# arduino-uno-shield.net
KiCad netlist of a schematic drawn in EAGLE
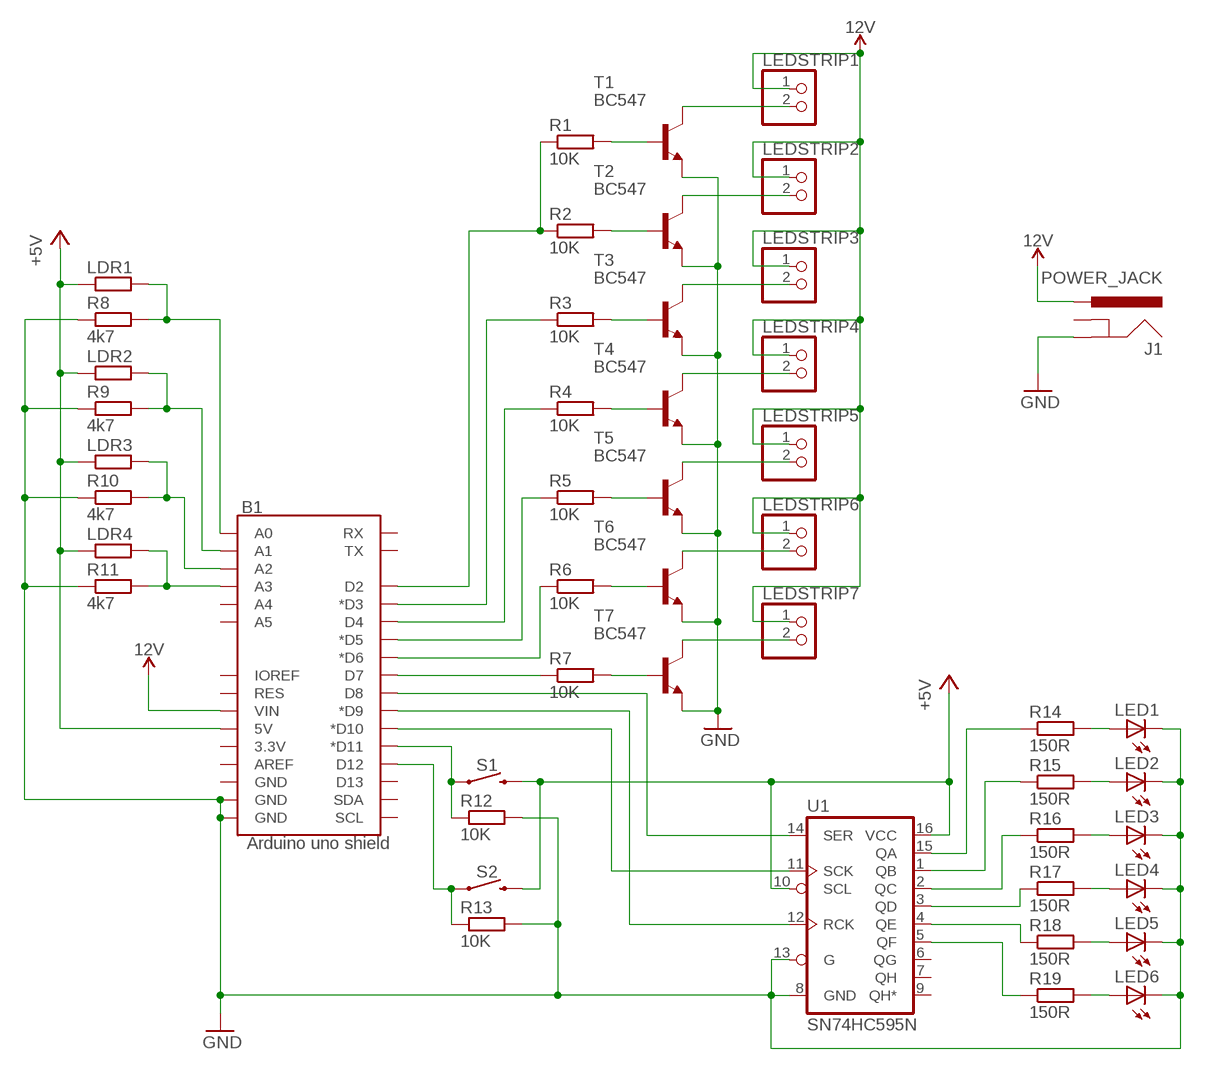
[diagram p0: schematic, sheet 1]

(export (version "E")
  (design (tool "Eeschema 10.0.6"))
  (components
    (comp (ref "B1")
      (value "Arduino uno shield")
      (footprint "eagle-import:UNO_R3_SHIELD_NOLABELS_LOCK")
      (libsource (lib "eagle-import") (part "ARDUINO_UNO_R3_SHIELDUNO_R3_SHIELD_NOLABELS_LOCK"))
    )
    (comp (ref "J1")
      (value "POWER_JACK")
      (footprint "eagle-import:POWER_JACK_PTH")
      (libsource (lib "eagle-import") (part "POWER_JACK"))
    )
    (comp (ref "LDR1")
      (value "R-EU_0204/5")
      (footprint "eagle-import:0204_5")
      (libsource (lib "eagle-import") (part "R-EU_0204/5"))
    )
    (comp (ref "LDR2")
      (value "R-EU_0204/5")
      (footprint "eagle-import:0204_5")
      (libsource (lib "eagle-import") (part "R-EU_0204/5"))
    )
    (comp (ref "LDR3")
      (value "R-EU_0204/5")
      (footprint "eagle-import:0204_5")
      (libsource (lib "eagle-import") (part "R-EU_0204/5"))
    )
    (comp (ref "LDR4")
      (value "R-EU_0204/5")
      (footprint "eagle-import:0204_5")
      (libsource (lib "eagle-import") (part "R-EU_0204/5"))
    )
    (comp (ref "LED1")
      (value "LED5MM")
      (footprint "eagle-import:LED5MM")
      (libsource (lib "eagle-import") (part "LED5MM"))
    )
    (comp (ref "LED2")
      (value "LED5MM")
      (footprint "eagle-import:LED5MM")
      (libsource (lib "eagle-import") (part "LED5MM"))
    )
    (comp (ref "LED3")
      (value "LED5MM")
      (footprint "eagle-import:LED5MM")
      (libsource (lib "eagle-import") (part "LED5MM"))
    )
    (comp (ref "LED4")
      (value "LED5MM")
      (footprint "eagle-import:LED5MM")
      (libsource (lib "eagle-import") (part "LED5MM"))
    )
    (comp (ref "LED5")
      (value "LED5MM")
      (footprint "eagle-import:LED5MM")
      (libsource (lib "eagle-import") (part "LED5MM"))
    )
    (comp (ref "LED6")
      (value "LED5MM")
      (footprint "eagle-import:LED5MM")
      (libsource (lib "eagle-import") (part "LED5MM"))
    )
    (comp (ref "LEDSTRIP1")
      (value "PINHD-1X2")
      (footprint "eagle-import:1X02")
      (libsource (lib "eagle-import") (part "PINHD-1X2"))
    )
    (comp (ref "LEDSTRIP2")
      (value "PINHD-1X2")
      (footprint "eagle-import:1X02")
      (libsource (lib "eagle-import") (part "PINHD-1X2"))
    )
    (comp (ref "LEDSTRIP3")
      (value "PINHD-1X2")
      (footprint "eagle-import:1X02")
      (libsource (lib "eagle-import") (part "PINHD-1X2"))
    )
    (comp (ref "LEDSTRIP4")
      (value "PINHD-1X2")
      (footprint "eagle-import:1X02")
      (libsource (lib "eagle-import") (part "PINHD-1X2"))
    )
    (comp (ref "LEDSTRIP5")
      (value "PINHD-1X2")
      (footprint "eagle-import:1X02")
      (libsource (lib "eagle-import") (part "PINHD-1X2"))
    )
    (comp (ref "LEDSTRIP6")
      (value "PINHD-1X2")
      (footprint "eagle-import:1X02")
      (libsource (lib "eagle-import") (part "PINHD-1X2"))
    )
    (comp (ref "LEDSTRIP7")
      (value "PINHD-1X2")
      (footprint "eagle-import:1X02")
      (libsource (lib "eagle-import") (part "PINHD-1X2"))
    )
    (comp (ref "R1")
      (value "10K")
      (footprint "eagle-import:0204_5")
      (libsource (lib "eagle-import") (part "R-EU_0204/5"))
    )
    (comp (ref "R2")
      (value "10K")
      (footprint "eagle-import:0204_5")
      (libsource (lib "eagle-import") (part "R-EU_0204/5"))
    )
    (comp (ref "R3")
      (value "10K")
      (footprint "eagle-import:0204_5")
      (libsource (lib "eagle-import") (part "R-EU_0204/5"))
    )
    (comp (ref "R4")
      (value "10K")
      (footprint "eagle-import:0204_5")
      (libsource (lib "eagle-import") (part "R-EU_0204/5"))
    )
    (comp (ref "R5")
      (value "10K")
      (footprint "eagle-import:0204_5")
      (libsource (lib "eagle-import") (part "R-EU_0204/5"))
    )
    (comp (ref "R6")
      (value "10K")
      (footprint "eagle-import:0204_5")
      (libsource (lib "eagle-import") (part "R-EU_0204/5"))
    )
    (comp (ref "R7")
      (value "10K")
      (footprint "eagle-import:0204_5")
      (libsource (lib "eagle-import") (part "R-EU_0204/5"))
    )
    (comp (ref "R8")
      (value "4k7")
      (footprint "eagle-import:0204_5")
      (libsource (lib "eagle-import") (part "R-EU_0204/5"))
    )
    (comp (ref "R9")
      (value "4k7")
      (footprint "eagle-import:0204_5")
      (libsource (lib "eagle-import") (part "R-EU_0204/5"))
    )
    (comp (ref "R10")
      (value "4k7")
      (footprint "eagle-import:0204_5")
      (libsource (lib "eagle-import") (part "R-EU_0204/5"))
    )
    (comp (ref "R11")
      (value "4k7")
      (footprint "eagle-import:0204_5")
      (libsource (lib "eagle-import") (part "R-EU_0204/5"))
    )
    (comp (ref "R12")
      (value "10K")
      (footprint "eagle-import:0204_5")
      (libsource (lib "eagle-import") (part "R-EU_0204/5"))
    )
    (comp (ref "R13")
      (value "10K")
      (footprint "eagle-import:0204_5")
      (libsource (lib "eagle-import") (part "R-EU_0204/5"))
    )
    (comp (ref "R14")
      (value "150R")
      (footprint "eagle-import:0204_5")
      (libsource (lib "eagle-import") (part "R-EU_0204/5"))
    )
    (comp (ref "R15")
      (value "150R")
      (footprint "eagle-import:0204_5")
      (libsource (lib "eagle-import") (part "R-EU_0204/5"))
    )
    (comp (ref "R16")
      (value "150R")
      (footprint "eagle-import:0204_5")
      (libsource (lib "eagle-import") (part "R-EU_0204/5"))
    )
    (comp (ref "R17")
      (value "150R")
      (footprint "eagle-import:0204_5")
      (libsource (lib "eagle-import") (part "R-EU_0204/5"))
    )
    (comp (ref "R18")
      (value "150R")
      (footprint "eagle-import:0204_5")
      (libsource (lib "eagle-import") (part "R-EU_0204/5"))
    )
    (comp (ref "R19")
      (value "150R")
      (footprint "eagle-import:0204_5")
      (libsource (lib "eagle-import") (part "R-EU_0204/5"))
    )
    (comp (ref "S1")
      (value "MOMENTARY-SWITCH-SPST-PTH-6.0MM")
      (footprint "eagle-import:TACTILE_SWITCH_PTH_6.0MM")
      (libsource (lib "eagle-import") (part "MOMENTARY-SWITCH-SPST-PTH-6.0MM"))
    )
    (comp (ref "S2")
      (value "MOMENTARY-SWITCH-SPST-PTH-6.0MM")
      (footprint "eagle-import:TACTILE_SWITCH_PTH_6.0MM")
      (libsource (lib "eagle-import") (part "MOMENTARY-SWITCH-SPST-PTH-6.0MM"))
    )
    (comp (ref "T1")
      (value "BC547")
      (footprint "eagle-import:TO92")
      (libsource (lib "eagle-import") (part "BC547"))
    )
    (comp (ref "T2")
      (value "BC547")
      (footprint "eagle-import:TO92")
      (libsource (lib "eagle-import") (part "BC547"))
    )
    (comp (ref "T3")
      (value "BC547")
      (footprint "eagle-import:TO92")
      (libsource (lib "eagle-import") (part "BC547"))
    )
    (comp (ref "T4")
      (value "BC547")
      (footprint "eagle-import:TO92")
      (libsource (lib "eagle-import") (part "BC547"))
    )
    (comp (ref "T5")
      (value "BC547")
      (footprint "eagle-import:TO92")
      (libsource (lib "eagle-import") (part "BC547"))
    )
    (comp (ref "T6")
      (value "BC547")
      (footprint "eagle-import:TO92")
      (libsource (lib "eagle-import") (part "BC547"))
    )
    (comp (ref "T7")
      (value "BC547")
      (footprint "eagle-import:TO92")
      (libsource (lib "eagle-import") (part "BC547"))
    )
    (comp (ref "U1")
      (value "SN74HC595N")
      (footprint "eagle-import:DIP16")
      (libsource (lib "eagle-import") (part "74595NHC"))
    )
  )
  (nets
    (net (code "1") (name "+5V") (class "Default")
      (node (ref "B1") (pin "5V") (pinfunction "5V_5V") (pintype "bidirectional"))
      (node (ref "LDR1") (pin "1") (pinfunction "1_1") (pintype "passive"))
      (node (ref "LDR2") (pin "1") (pinfunction "1_1") (pintype "passive"))
      (node (ref "LDR3") (pin "1") (pinfunction "1_1") (pintype "passive"))
      (node (ref "LDR4") (pin "1") (pinfunction "1_1") (pintype "passive"))
      (node (ref "S1") (pin "3") (pinfunction "2_3") (pintype "passive"))
      (node (ref "S2") (pin "3") (pinfunction "2_3") (pintype "passive"))
      (node (ref "U1") (pin "10") (pinfunction "SCL_10") (pintype "input"))
      (node (ref "U1") (pin "16") (pinfunction "VCC_16") (pintype "power_in"))
    )
    (net (code "2") (name "12V") (class "Default")
      (node (ref "B1") (pin "VIN") (pinfunction "VIN_VIN") (pintype "bidirectional"))
      (node (ref "J1") (pin "PWR") (pinfunction "PWR_PWR") (pintype "bidirectional"))
      (node (ref "LEDSTRIP1") (pin "1") (pinfunction "1_1") (pintype "passive"))
      (node (ref "LEDSTRIP2") (pin "1") (pinfunction "1_1") (pintype "passive"))
      (node (ref "LEDSTRIP3") (pin "1") (pinfunction "1_1") (pintype "passive"))
      (node (ref "LEDSTRIP4") (pin "1") (pinfunction "1_1") (pintype "passive"))
      (node (ref "LEDSTRIP5") (pin "1") (pinfunction "1_1") (pintype "passive"))
      (node (ref "LEDSTRIP6") (pin "1") (pinfunction "1_1") (pintype "passive"))
      (node (ref "LEDSTRIP7") (pin "1") (pinfunction "1_1") (pintype "passive"))
    )
    (net (code "3") (name "GND") (class "Default")
      (node (ref "B1") (pin "GND@0") (pinfunction "GND_GND@0") (pintype "bidirectional"))
      (node (ref "B1") (pin "GND@1") (pinfunction "GND_GND@1") (pintype "bidirectional"))
      (node (ref "J1") (pin "GND") (pinfunction "GND_GND") (pintype "bidirectional"))
      (node (ref "LED1") (pin "K") (pinfunction "C_K") (pintype "passive"))
      (node (ref "LED2") (pin "K") (pinfunction "C_K") (pintype "passive"))
      (node (ref "LED3") (pin "K") (pinfunction "C_K") (pintype "passive"))
      (node (ref "LED4") (pin "K") (pinfunction "C_K") (pintype "passive"))
      (node (ref "LED5") (pin "K") (pinfunction "C_K") (pintype "passive"))
      (node (ref "LED6") (pin "K") (pinfunction "C_K") (pintype "passive"))
      (node (ref "R10") (pin "1") (pinfunction "1_1") (pintype "passive"))
      (node (ref "R11") (pin "1") (pinfunction "1_1") (pintype "passive"))
      (node (ref "R12") (pin "2") (pinfunction "2_2") (pintype "passive"))
      (node (ref "R13") (pin "2") (pinfunction "2_2") (pintype "passive"))
      (node (ref "R8") (pin "1") (pinfunction "1_1") (pintype "passive"))
      (node (ref "R9") (pin "1") (pinfunction "1_1") (pintype "passive"))
      (node (ref "T1") (pin "1") (pinfunction "E_1") (pintype "passive"))
      (node (ref "T2") (pin "1") (pinfunction "E_1") (pintype "passive"))
      (node (ref "T3") (pin "1") (pinfunction "E_1") (pintype "passive"))
      (node (ref "T4") (pin "1") (pinfunction "E_1") (pintype "passive"))
      (node (ref "T5") (pin "1") (pinfunction "E_1") (pintype "passive"))
      (node (ref "T6") (pin "1") (pinfunction "E_1") (pintype "passive"))
      (node (ref "T7") (pin "1") (pinfunction "E_1") (pintype "passive"))
      (node (ref "U1") (pin "13") (pinfunction "G_13") (pintype "input"))
      (node (ref "U1") (pin "8") (pinfunction "GND_8") (pintype "power_in"))
    )
    (net (code "4") (name "Net-(B1-*D3)") (class "Default")
      (node (ref "B1") (pin "D3") (pinfunction "*D3_D3") (pintype "bidirectional"))
      (node (ref "R3") (pin "1") (pinfunction "1_1") (pintype "passive"))
    )
    (net (code "5") (name "Net-(B1-*D5)") (class "Default")
      (node (ref "B1") (pin "D5") (pinfunction "*D5_D5") (pintype "bidirectional"))
      (node (ref "R5") (pin "1") (pinfunction "1_1") (pintype "passive"))
    )
    (net (code "6") (name "Net-(B1-*D6)") (class "Default")
      (node (ref "B1") (pin "D6") (pinfunction "*D6_D6") (pintype "bidirectional"))
      (node (ref "R6") (pin "1") (pinfunction "1_1") (pintype "passive"))
    )
    (net (code "7") (name "Net-(B1-*D9)") (class "Default")
      (node (ref "B1") (pin "D9") (pinfunction "*D9_D9") (pintype "bidirectional"))
      (node (ref "U1") (pin "12") (pinfunction "RCK_12") (pintype "input"))
    )
    (net (code "8") (name "Net-(B1-*D10)") (class "Default")
      (node (ref "B1") (pin "D10") (pinfunction "*D10_D10") (pintype "bidirectional"))
      (node (ref "U1") (pin "11") (pinfunction "SCK_11") (pintype "input"))
    )
    (net (code "9") (name "Net-(B1-*D11)") (class "Default")
      (node (ref "B1") (pin "D11") (pinfunction "*D11_D11") (pintype "bidirectional"))
      (node (ref "R12") (pin "1") (pinfunction "1_1") (pintype "passive"))
      (node (ref "S1") (pin "1") (pinfunction "1_1") (pintype "passive"))
    )
    (net (code "10") (name "Net-(B1-PadA0)") (class "Default")
      (node (ref "B1") (pin "A0") (pinfunction "A0_A0") (pintype "bidirectional"))
      (node (ref "LDR1") (pin "2") (pinfunction "2_2") (pintype "passive"))
      (node (ref "R8") (pin "2") (pinfunction "2_2") (pintype "passive"))
    )
    (net (code "11") (name "Net-(B1-PadA1)") (class "Default")
      (node (ref "B1") (pin "A1") (pinfunction "A1_A1") (pintype "bidirectional"))
      (node (ref "LDR2") (pin "2") (pinfunction "2_2") (pintype "passive"))
      (node (ref "R9") (pin "2") (pinfunction "2_2") (pintype "passive"))
    )
    (net (code "12") (name "Net-(B1-PadA2)") (class "Default")
      (node (ref "B1") (pin "A2") (pinfunction "A2_A2") (pintype "bidirectional"))
      (node (ref "LDR3") (pin "2") (pinfunction "2_2") (pintype "passive"))
      (node (ref "R10") (pin "2") (pinfunction "2_2") (pintype "passive"))
    )
    (net (code "13") (name "Net-(B1-PadA3)") (class "Default")
      (node (ref "B1") (pin "A3") (pinfunction "A3_A3") (pintype "bidirectional"))
      (node (ref "LDR4") (pin "2") (pinfunction "2_2") (pintype "passive"))
      (node (ref "R11") (pin "2") (pinfunction "2_2") (pintype "passive"))
    )
    (net (code "14") (name "Net-(B1-PadD2)") (class "Default")
      (node (ref "B1") (pin "D2") (pinfunction "D2_D2") (pintype "bidirectional"))
      (node (ref "R1") (pin "1") (pinfunction "1_1") (pintype "passive"))
      (node (ref "R2") (pin "1") (pinfunction "1_1") (pintype "passive"))
    )
    (net (code "15") (name "Net-(B1-PadD4)") (class "Default")
      (node (ref "B1") (pin "D4") (pinfunction "D4_D4") (pintype "bidirectional"))
      (node (ref "R4") (pin "1") (pinfunction "1_1") (pintype "passive"))
    )
    (net (code "16") (name "Net-(B1-PadD7)") (class "Default")
      (node (ref "B1") (pin "D7") (pinfunction "D7_D7") (pintype "bidirectional"))
      (node (ref "R7") (pin "1") (pinfunction "1_1") (pintype "passive"))
    )
    (net (code "17") (name "Net-(B1-PadD12)") (class "Default")
      (node (ref "B1") (pin "D12") (pinfunction "D12_D12") (pintype "bidirectional"))
      (node (ref "R13") (pin "1") (pinfunction "1_1") (pintype "passive"))
      (node (ref "S2") (pin "1") (pinfunction "1_1") (pintype "passive"))
    )
    (net (code "18") (name "Net-(LED1-PadA)") (class "Default")
      (node (ref "LED1") (pin "A") (pinfunction "A_A") (pintype "passive"))
      (node (ref "R14") (pin "2") (pinfunction "2_2") (pintype "passive"))
    )
    (net (code "19") (name "Net-(LED2-PadA)") (class "Default")
      (node (ref "LED2") (pin "A") (pinfunction "A_A") (pintype "passive"))
      (node (ref "R15") (pin "2") (pinfunction "2_2") (pintype "passive"))
    )
    (net (code "20") (name "Net-(LED3-PadA)") (class "Default")
      (node (ref "LED3") (pin "A") (pinfunction "A_A") (pintype "passive"))
      (node (ref "R16") (pin "2") (pinfunction "2_2") (pintype "passive"))
    )
    (net (code "21") (name "Net-(LED4-PadA)") (class "Default")
      (node (ref "LED4") (pin "A") (pinfunction "A_A") (pintype "passive"))
      (node (ref "R17") (pin "2") (pinfunction "2_2") (pintype "passive"))
    )
    (net (code "22") (name "Net-(LED5-PadA)") (class "Default")
      (node (ref "LED5") (pin "A") (pinfunction "A_A") (pintype "passive"))
      (node (ref "R18") (pin "2") (pinfunction "2_2") (pintype "passive"))
    )
    (net (code "23") (name "Net-(LED6-PadA)") (class "Default")
      (node (ref "LED6") (pin "A") (pinfunction "A_A") (pintype "passive"))
      (node (ref "R19") (pin "2") (pinfunction "2_2") (pintype "passive"))
    )
    (net (code "24") (name "Net-(T1-B)") (class "Default")
      (node (ref "R1") (pin "2") (pinfunction "2_2") (pintype "passive"))
      (node (ref "T1") (pin "2") (pinfunction "B_2") (pintype "passive"))
    )
    (net (code "25") (name "Net-(T1-C)") (class "Default")
      (node (ref "LEDSTRIP1") (pin "2") (pinfunction "2_2") (pintype "passive"))
      (node (ref "T1") (pin "3") (pinfunction "C_3") (pintype "passive"))
    )
    (net (code "26") (name "Net-(T2-B)") (class "Default")
      (node (ref "R2") (pin "2") (pinfunction "2_2") (pintype "passive"))
      (node (ref "T2") (pin "2") (pinfunction "B_2") (pintype "passive"))
    )
    (net (code "27") (name "Net-(T2-C)") (class "Default")
      (node (ref "LEDSTRIP2") (pin "2") (pinfunction "2_2") (pintype "passive"))
      (node (ref "T2") (pin "3") (pinfunction "C_3") (pintype "passive"))
    )
    (net (code "28") (name "Net-(T3-B)") (class "Default")
      (node (ref "R3") (pin "2") (pinfunction "2_2") (pintype "passive"))
      (node (ref "T3") (pin "2") (pinfunction "B_2") (pintype "passive"))
    )
    (net (code "29") (name "Net-(T3-C)") (class "Default")
      (node (ref "LEDSTRIP3") (pin "2") (pinfunction "2_2") (pintype "passive"))
      (node (ref "T3") (pin "3") (pinfunction "C_3") (pintype "passive"))
    )
    (net (code "30") (name "Net-(T4-B)") (class "Default")
      (node (ref "R4") (pin "2") (pinfunction "2_2") (pintype "passive"))
      (node (ref "T4") (pin "2") (pinfunction "B_2") (pintype "passive"))
    )
    (net (code "31") (name "Net-(T4-C)") (class "Default")
      (node (ref "LEDSTRIP4") (pin "2") (pinfunction "2_2") (pintype "passive"))
      (node (ref "T4") (pin "3") (pinfunction "C_3") (pintype "passive"))
    )
    (net (code "32") (name "Net-(T5-B)") (class "Default")
      (node (ref "R5") (pin "2") (pinfunction "2_2") (pintype "passive"))
      (node (ref "T5") (pin "2") (pinfunction "B_2") (pintype "passive"))
    )
    (net (code "33") (name "Net-(T5-C)") (class "Default")
      (node (ref "LEDSTRIP5") (pin "2") (pinfunction "2_2") (pintype "passive"))
      (node (ref "T5") (pin "3") (pinfunction "C_3") (pintype "passive"))
    )
    (net (code "34") (name "Net-(T6-B)") (class "Default")
      (node (ref "R6") (pin "2") (pinfunction "2_2") (pintype "passive"))
      (node (ref "T6") (pin "2") (pinfunction "B_2") (pintype "passive"))
    )
    (net (code "35") (name "Net-(T6-C)") (class "Default")
      (node (ref "LEDSTRIP6") (pin "2") (pinfunction "2_2") (pintype "passive"))
      (node (ref "T6") (pin "3") (pinfunction "C_3") (pintype "passive"))
    )
    (net (code "36") (name "Net-(T7-B)") (class "Default")
      (node (ref "R7") (pin "2") (pinfunction "2_2") (pintype "passive"))
      (node (ref "T7") (pin "2") (pinfunction "B_2") (pintype "passive"))
    )
    (net (code "37") (name "Net-(T7-C)") (class "Default")
      (node (ref "LEDSTRIP7") (pin "2") (pinfunction "2_2") (pintype "passive"))
      (node (ref "T7") (pin "3") (pinfunction "C_3") (pintype "passive"))
    )
    (net (code "38") (name "Net-(U1-QA)") (class "Default")
      (node (ref "R14") (pin "1") (pinfunction "1_1") (pintype "passive"))
      (node (ref "U1") (pin "15") (pinfunction "QA_15") (pintype "tri_state"))
    )
    (net (code "39") (name "Net-(U1-QB)") (class "Default")
      (node (ref "R15") (pin "1") (pinfunction "1_1") (pintype "passive"))
      (node (ref "U1") (pin "1") (pinfunction "QB_1") (pintype "tri_state"))
    )
    (net (code "40") (name "Net-(U1-QC)") (class "Default")
      (node (ref "R16") (pin "1") (pinfunction "1_1") (pintype "passive"))
      (node (ref "U1") (pin "2") (pinfunction "QC_2") (pintype "tri_state"))
    )
    (net (code "41") (name "Net-(U1-QD)") (class "Default")
      (node (ref "R17") (pin "1") (pinfunction "1_1") (pintype "passive"))
      (node (ref "U1") (pin "3") (pinfunction "QD_3") (pintype "tri_state"))
    )
    (net (code "42") (name "Net-(U1-QE)") (class "Default")
      (node (ref "R18") (pin "1") (pinfunction "1_1") (pintype "passive"))
      (node (ref "U1") (pin "4") (pinfunction "QE_4") (pintype "tri_state"))
    )
    (net (code "43") (name "Net-(U1-QF)") (class "Default")
      (node (ref "R19") (pin "1") (pinfunction "1_1") (pintype "passive"))
      (node (ref "U1") (pin "5") (pinfunction "QF_5") (pintype "tri_state"))
    )
    (net (code "44") (name "Net-(U1-SER)") (class "Default")
      (node (ref "B1") (pin "D8") (pinfunction "D8_D8") (pintype "bidirectional"))
      (node (ref "U1") (pin "14") (pinfunction "SER_14") (pintype "input"))
    )
    (net (code "45") (name "unconnected-(B1-GND-PadGND@2)") (class "Default")
      (node (ref "B1") (pin "GND@2") (pinfunction "GND_GND@2") (pintype "bidirectional"))
    )
    (net (code "46") (name "unconnected-(B1-Pad3.3V)") (class "Default")
      (node (ref "B1") (pin "3.3V") (pinfunction "3.3V_3.3V") (pintype "bidirectional"))
    )
    (net (code "47") (name "unconnected-(B1-PadA4)") (class "Default")
      (node (ref "B1") (pin "A4") (pinfunction "A4_A4") (pintype "bidirectional"))
    )
    (net (code "48") (name "unconnected-(B1-PadA5)") (class "Default")
      (node (ref "B1") (pin "A5") (pinfunction "A5_A5") (pintype "bidirectional"))
    )
    (net (code "49") (name "unconnected-(B1-PadAREF)") (class "Default")
      (node (ref "B1") (pin "AREF") (pinfunction "AREF_AREF") (pintype "bidirectional"))
    )
    (net (code "50") (name "unconnected-(B1-PadD13)") (class "Default")
      (node (ref "B1") (pin "D13") (pinfunction "D13_D13") (pintype "bidirectional"))
    )
    (net (code "51") (name "unconnected-(B1-PadIOREF)") (class "Default")
      (node (ref "B1") (pin "IOREF") (pinfunction "IOREF_IOREF") (pintype "bidirectional"))
    )
    (net (code "52") (name "unconnected-(B1-PadRES)") (class "Default")
      (node (ref "B1") (pin "RES") (pinfunction "RES_RES") (pintype "bidirectional"))
    )
    (net (code "53") (name "unconnected-(B1-PadRX)") (class "Default")
      (node (ref "B1") (pin "RX") (pinfunction "RX_RX") (pintype "bidirectional"))
    )
    (net (code "54") (name "unconnected-(B1-PadSCL)") (class "Default")
      (node (ref "B1") (pin "SCL") (pinfunction "SCL_SCL") (pintype "bidirectional"))
    )
    (net (code "55") (name "unconnected-(B1-PadSDA)") (class "Default")
      (node (ref "B1") (pin "SDA") (pinfunction "SDA_SDA") (pintype "bidirectional"))
    )
    (net (code "56") (name "unconnected-(B1-PadTX)") (class "Default")
      (node (ref "B1") (pin "TX") (pinfunction "TX_TX") (pintype "bidirectional"))
    )
    (net (code "57") (name "unconnected-(J1-PadGNDBREAK)") (class "Default")
      (node (ref "J1") (pin "GNDBREAK") (pinfunction "GNDBREAK_GNDBREAK") (pintype "bidirectional"))
    )
    (net (code "58") (name "unconnected-(U1-QG-Pad6)") (class "Default")
      (node (ref "U1") (pin "6") (pinfunction "QG_6") (pintype "tri_state"))
    )
    (net (code "59") (name "unconnected-(U1-QH*-Pad9)") (class "Default")
      (node (ref "U1") (pin "9") (pinfunction "QH*_9") (pintype "tri_state"))
    )
    (net (code "60") (name "unconnected-(U1-QH-Pad7)") (class "Default")
      (node (ref "U1") (pin "7") (pinfunction "QH_7") (pintype "tri_state"))
    )
  )
)
